# rf_lpf.net
KiCad netlist of a schematic drawn in Altium Designer
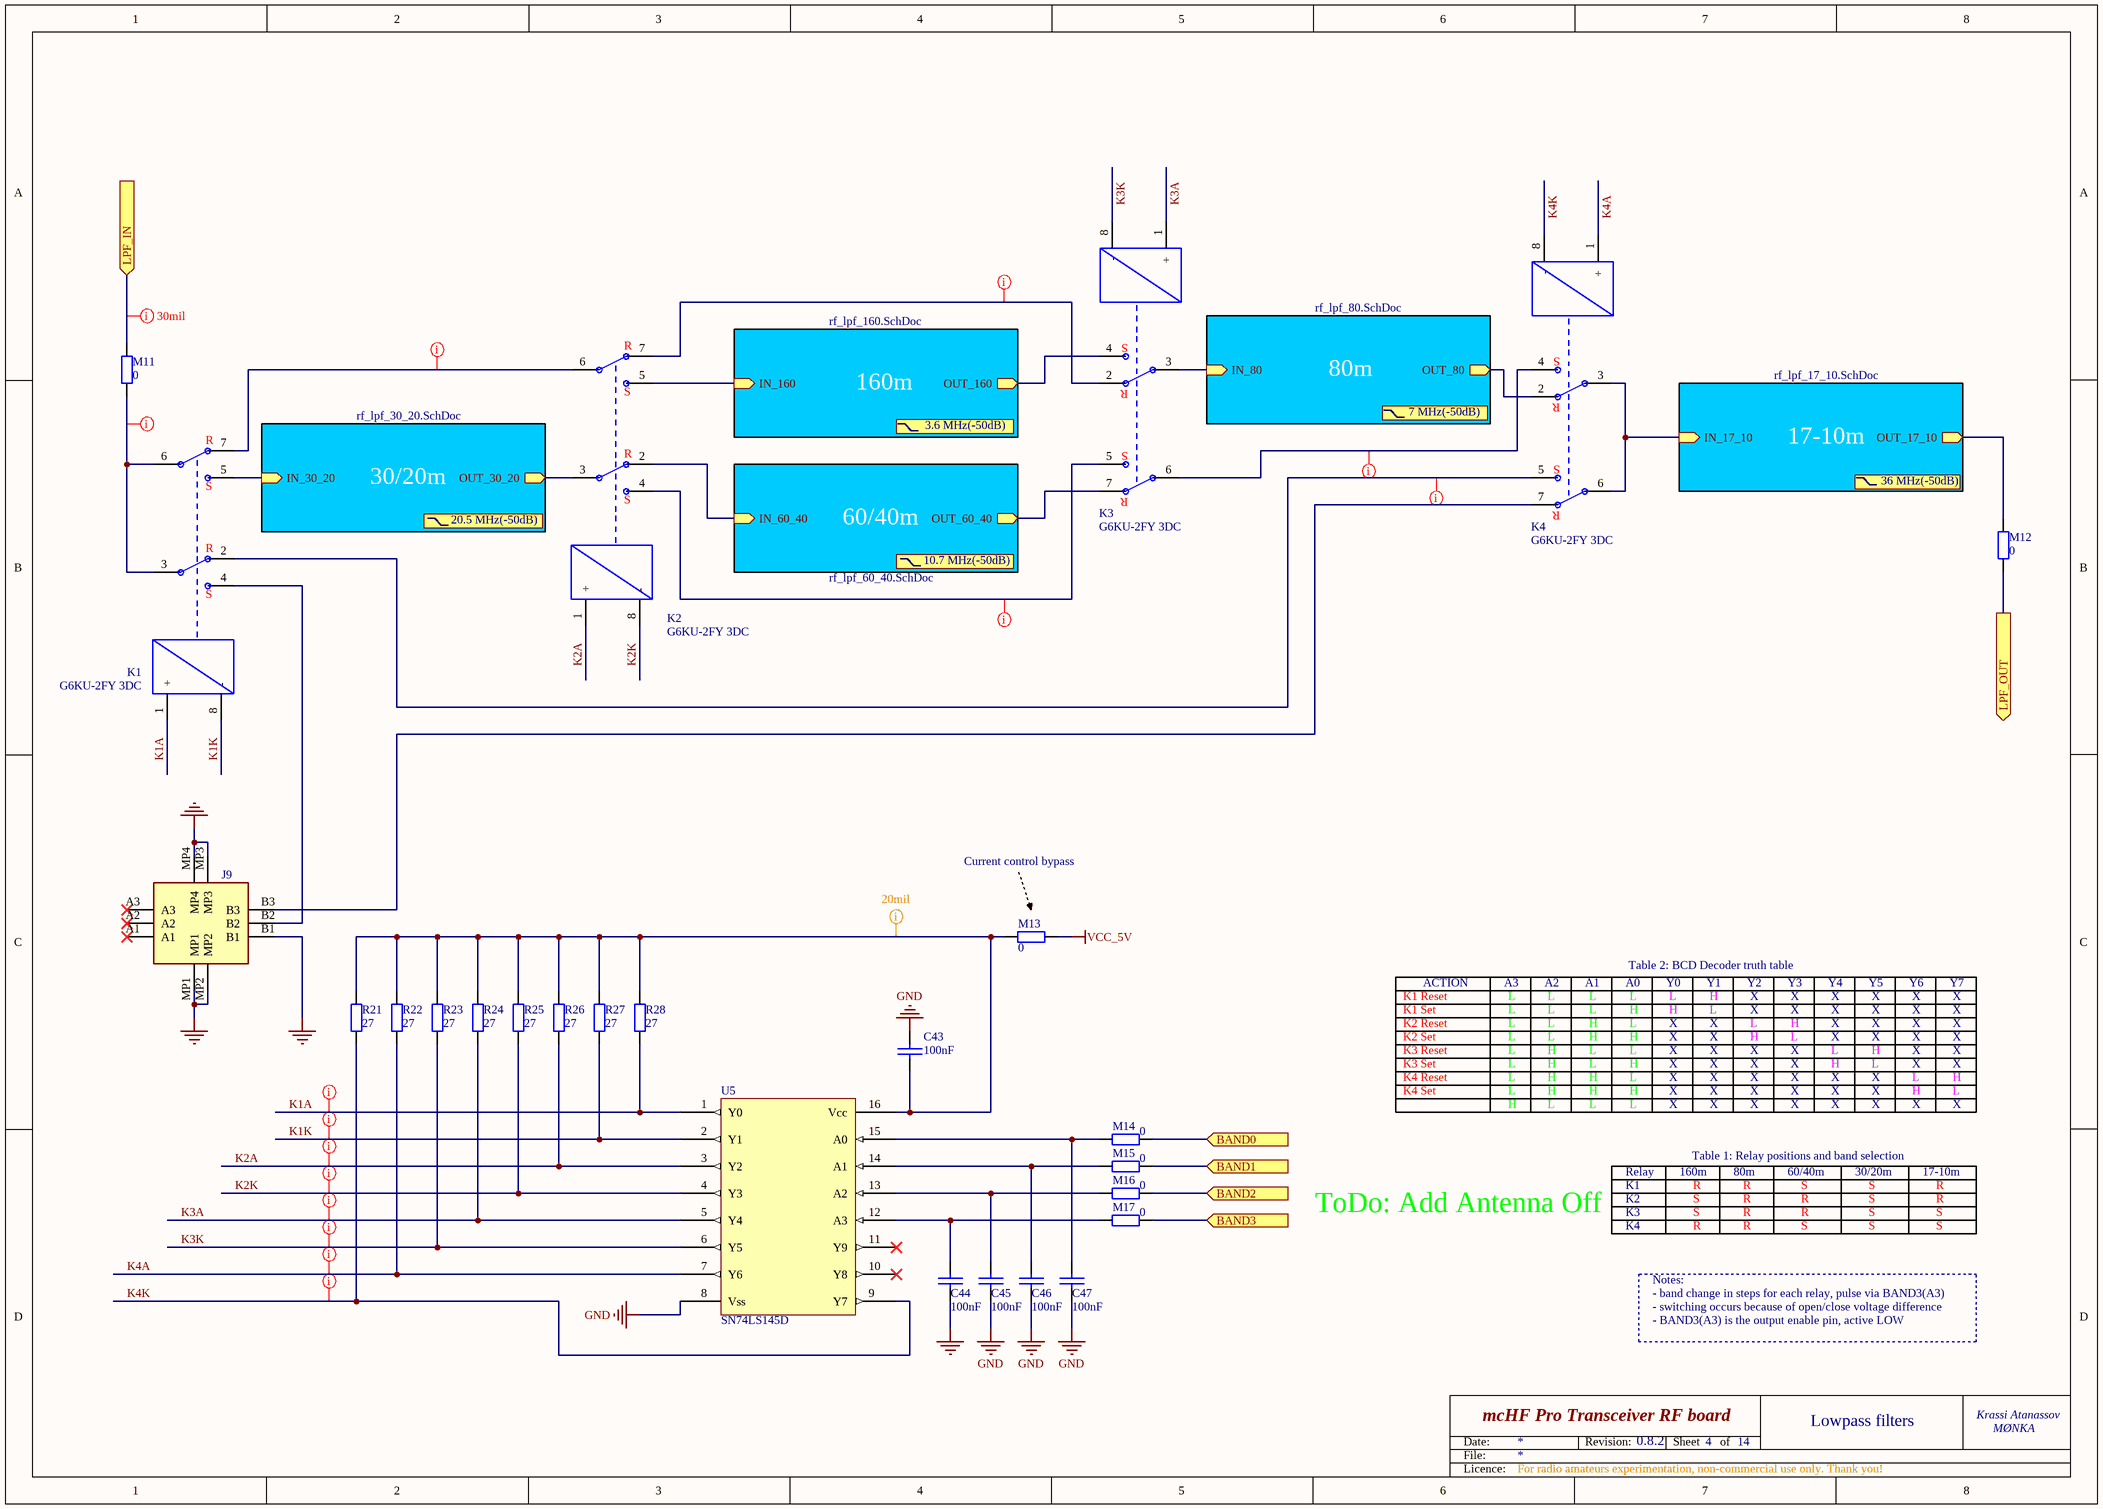
[diagram p0: rf_lpf.SchDoc]

(export (version "E")
  (design (tool "Eeschema 10.0.6"))
  (components
    (comp (ref "C43")
      (value "100nF")
      (footprint "0805")
      (description "Capacitor")
      (libsource (lib "mcHF_rf") (part "CAP"))
    )
    (comp (ref "C44")
      (value "100nF")
      (footprint "0805")
      (description "Capacitor")
      (libsource (lib "mcHF_rf") (part "CAP"))
    )
    (comp (ref "C45")
      (value "100nF")
      (footprint "0805")
      (description "Capacitor")
      (libsource (lib "mcHF_rf") (part "CAP"))
    )
    (comp (ref "C46")
      (value "100nF")
      (footprint "0805")
      (description "Capacitor")
      (libsource (lib "mcHF_rf") (part "CAP"))
    )
    (comp (ref "C47")
      (value "100nF")
      (footprint "0805")
      (description "Capacitor")
      (libsource (lib "mcHF_rf") (part "CAP"))
    )
    (comp (ref "J9")
      (value "1373826")
      (footprint "1373826")
      (fields (field (name "MOUSER PART NUMBER") "651-1373826"))
      (libsource (lib "1373826") (part "1373826"))
    )
    (comp (ref "K1")
      (value "G6KU-2FY 3DC")
      (footprint "Omron_2FY-Pro")
      (description "Single-winding Latching Relay")
      (libsource (lib "__rf") (part "G6KU-2FY 3DC"))
    )
    (comp (ref "K2")
      (value "G6KU-2FY 3DC")
      (footprint "Omron_2FY-Pro")
      (description "Single-winding Latching Relay")
      (libsource (lib "__rf") (part "G6KU-2FY 3DC"))
    )
    (comp (ref "K3")
      (value "G6KU-2FY 3DC")
      (footprint "Omron_2FY-Pro")
      (description "Single-winding Latching Relay")
      (libsource (lib "__rf") (part "G6KU-2FY 3DC"))
    )
    (comp (ref "K4")
      (value "G6KU-2FY 3DC")
      (footprint "Omron_2FY-Pro")
      (description "Single-winding Latching Relay")
      (libsource (lib "__rf") (part "G6KU-2FY 3DC"))
    )
    (comp (ref "M11")
      (value "0")
      (footprint "0805")
      (description "Resistor")
      (libsource (lib "") (part "RES_2"))
    )
    (comp (ref "M12")
      (value "0")
      (footprint "0805")
      (description "Resistor")
      (libsource (lib "") (part "RES_1"))
    )
    (comp (ref "M13")
      (value "0")
      (footprint "0805")
      (description "Resistor")
      (libsource (lib "") (part "RES_3"))
    )
    (comp (ref "M14")
      (value "0")
      (footprint "0805")
      (description "Resistor")
      (libsource (lib "mcHF_rf") (part "RES"))
    )
    (comp (ref "M15")
      (value "0")
      (footprint "0805")
      (description "Resistor")
      (libsource (lib "mcHF_rf") (part "RES"))
    )
    (comp (ref "M16")
      (value "0")
      (footprint "0805")
      (description "Resistor")
      (libsource (lib "mcHF_rf") (part "RES"))
    )
    (comp (ref "M17")
      (value "0")
      (footprint "0805")
      (description "Resistor")
      (libsource (lib "mcHF_rf") (part "RES"))
    )
    (comp (ref "R21")
      (value "27")
      (footprint "1206")
      (description "Resistor")
      (libsource (lib "") (part "RES_2"))
    )
    (comp (ref "R22")
      (value "27")
      (footprint "1206")
      (description "Resistor")
      (libsource (lib "") (part "RES_2"))
    )
    (comp (ref "R23")
      (value "27")
      (footprint "1206")
      (description "Resistor")
      (libsource (lib "") (part "RES_2"))
    )
    (comp (ref "R24")
      (value "27")
      (footprint "1206")
      (description "Resistor")
      (libsource (lib "") (part "RES_2"))
    )
    (comp (ref "R25")
      (value "27")
      (footprint "1206")
      (description "Resistor")
      (libsource (lib "") (part "RES_2"))
    )
    (comp (ref "R26")
      (value "27")
      (footprint "1206")
      (description "Resistor")
      (libsource (lib "") (part "RES_2"))
    )
    (comp (ref "R27")
      (value "27")
      (footprint "1206")
      (description "Resistor")
      (libsource (lib "") (part "RES_2"))
    )
    (comp (ref "R28")
      (value "27")
      (footprint "1206")
      (description "Resistor")
      (libsource (lib "") (part "RES_2"))
    )
    (comp (ref "U5")
      (value "SN74LS145D")
      (footprint "SO-16")
      (description "BCD DECODER/DRIVER")
      (libsource (lib "mcHF_rf") (part "SN74LS145D"))
    )
  )
  (nets
    (net (code "1") (name "/BAND0") (class "Default")
      (node (ref "M14") (pin "1") (pinfunction "1_1") (pintype "passive"))
    )
    (net (code "2") (name "/BAND1") (class "Default")
      (node (ref "M15") (pin "1") (pinfunction "1_1") (pintype "passive"))
    )
    (net (code "3") (name "/BAND2") (class "Default")
      (node (ref "M16") (pin "1") (pinfunction "1_1") (pintype "passive"))
    )
    (net (code "4") (name "/BAND3") (class "Default")
      (node (ref "M17") (pin "1") (pinfunction "1_1") (pintype "passive"))
    )
    (net (code "5") (name "/IN_17_10") (class "Default")
      (node (ref "K4") (pin "3") (pinfunction "3_3") (pintype "passive"))
      (node (ref "K4") (pin "6") (pinfunction "6_6") (pintype "passive"))
    )
    (net (code "6") (name "/IN_30_20") (class "Default")
      (node (ref "K1") (pin "5") (pinfunction "5_5") (pintype "passive"))
    )
    (net (code "7") (name "/IN_60_40") (class "Default")
      (node (ref "K2") (pin "2") (pinfunction "2_2") (pintype "passive"))
    )
    (net (code "8") (name "/IN_80") (class "Default")
      (node (ref "K3") (pin "3") (pinfunction "3_3") (pintype "passive"))
    )
    (net (code "9") (name "/IN_160") (class "Default")
      (node (ref "K2") (pin "5") (pinfunction "5_5") (pintype "passive"))
    )
    (net (code "10") (name "/K1A") (class "Default")
      (node (ref "K1") (pin "1") (pinfunction "+_1") (pintype "passive"))
      (node (ref "R28") (pin "1") (pinfunction "1_1") (pintype "passive"))
      (node (ref "U5") (pin "1") (pinfunction "Y0_1") (pintype "output"))
    )
    (net (code "11") (name "/K1K") (class "Default")
      (node (ref "K1") (pin "8") (pinfunction "-_8") (pintype "passive"))
      (node (ref "R27") (pin "1") (pinfunction "1_1") (pintype "passive"))
      (node (ref "U5") (pin "2") (pinfunction "Y1_2") (pintype "output"))
    )
    (net (code "12") (name "/K2A") (class "Default")
      (node (ref "K2") (pin "1") (pinfunction "+_1") (pintype "passive"))
      (node (ref "R26") (pin "1") (pinfunction "1_1") (pintype "passive"))
      (node (ref "U5") (pin "3") (pinfunction "Y2_3") (pintype "output"))
    )
    (net (code "13") (name "/K2K") (class "Default")
      (node (ref "K2") (pin "8") (pinfunction "-_8") (pintype "passive"))
      (node (ref "R25") (pin "1") (pinfunction "1_1") (pintype "passive"))
      (node (ref "U5") (pin "4") (pinfunction "Y3_4") (pintype "output"))
    )
    (net (code "14") (name "/K3A") (class "Default")
      (node (ref "K3") (pin "1") (pinfunction "+_1") (pintype "passive"))
      (node (ref "R24") (pin "1") (pinfunction "1_1") (pintype "passive"))
      (node (ref "U5") (pin "5") (pinfunction "Y4_5") (pintype "output"))
    )
    (net (code "15") (name "/K3K") (class "Default")
      (node (ref "K3") (pin "8") (pinfunction "-_8") (pintype "passive"))
      (node (ref "R23") (pin "1") (pinfunction "1_1") (pintype "passive"))
      (node (ref "U5") (pin "6") (pinfunction "Y5_6") (pintype "output"))
    )
    (net (code "16") (name "/K4A") (class "Default")
      (node (ref "K4") (pin "1") (pinfunction "+_1") (pintype "passive"))
      (node (ref "R22") (pin "1") (pinfunction "1_1") (pintype "passive"))
      (node (ref "U5") (pin "7") (pinfunction "Y6_7") (pintype "output"))
    )
    (net (code "17") (name "/K4K") (class "Default")
      (node (ref "K4") (pin "8") (pinfunction "-_8") (pintype "passive"))
      (node (ref "R21") (pin "1") (pinfunction "1_1") (pintype "passive"))
      (node (ref "U5") (pin "9") (pinfunction "Y7_9") (pintype "output"))
    )
    (net (code "18") (name "/LPF_IN") (class "Default")
      (node (ref "M11") (pin "2") (pinfunction "2_2") (pintype "passive"))
    )
    (net (code "19") (name "/LPF_OUT") (class "Default")
      (node (ref "M12") (pin "2") (pinfunction "2_2") (pintype "passive"))
    )
    (net (code "20") (name "/OUT_17_10") (class "Default")
      (node (ref "M12") (pin "1") (pinfunction "1_1") (pintype "passive"))
    )
    (net (code "21") (name "/OUT_30_20") (class "Default")
      (node (ref "K2") (pin "3") (pinfunction "3_3") (pintype "passive"))
    )
    (net (code "22") (name "/OUT_60_40") (class "Default")
      (node (ref "K3") (pin "7") (pinfunction "7_7") (pintype "passive"))
    )
    (net (code "23") (name "/OUT_80") (class "Default")
      (node (ref "K4") (pin "2") (pinfunction "2_2") (pintype "passive"))
    )
    (net (code "24") (name "/OUT_160") (class "Default")
      (node (ref "K3") (pin "4") (pinfunction "4_4") (pintype "passive"))
    )
    (net (code "25") (name "GND") (class "Default")
      (node (ref "C43") (pin "2") (pinfunction "2_2") (pintype "passive"))
      (node (ref "C44") (pin "1") (pinfunction "1_1") (pintype "passive"))
      (node (ref "C45") (pin "1") (pinfunction "1_1") (pintype "passive"))
      (node (ref "C46") (pin "1") (pinfunction "1_1") (pintype "passive"))
      (node (ref "C47") (pin "1") (pinfunction "1_1") (pintype "passive"))
      (node (ref "J9") (pin "B1") (pinfunction "B1_B1") (pintype "passive"))
      (node (ref "J9") (pin "MP1") (pinfunction "MP1_MP1") (pintype "passive"))
      (node (ref "J9") (pin "MP2") (pinfunction "MP2_MP2") (pintype "passive"))
      (node (ref "J9") (pin "MP3") (pinfunction "MP3_MP3") (pintype "passive"))
      (node (ref "J9") (pin "MP4") (pinfunction "MP4_MP4") (pintype "passive"))
      (node (ref "U5") (pin "8") (pinfunction "Vss_8") (pintype "power_in"))
    )
    (net (code "26") (name "Net-(J9-PadB2)") (class "Default")
      (node (ref "J9") (pin "B2") (pinfunction "B2_B2") (pintype "passive"))
      (node (ref "K1") (pin "4") (pinfunction "4_4") (pintype "passive"))
    )
    (net (code "27") (name "Net-(J9-PadB3)") (class "Default")
      (node (ref "J9") (pin "B3") (pinfunction "B3_B3") (pintype "passive"))
      (node (ref "K4") (pin "7") (pinfunction "7_7") (pintype "passive"))
    )
    (net (code "28") (name "Net-(K1-Pad2)") (class "Default")
      (node (ref "K1") (pin "2") (pinfunction "2_2") (pintype "passive"))
      (node (ref "K4") (pin "5") (pinfunction "5_5") (pintype "passive"))
    )
    (net (code "29") (name "Net-(K1-Pad3)") (class "Default")
      (node (ref "K1") (pin "3") (pinfunction "3_3") (pintype "passive"))
      (node (ref "K1") (pin "6") (pinfunction "6_6") (pintype "passive"))
      (node (ref "M11") (pin "1") (pinfunction "1_1") (pintype "passive"))
    )
    (net (code "30") (name "Net-(K1-Pad7)") (class "Default")
      (node (ref "K1") (pin "7") (pinfunction "7_7") (pintype "passive"))
      (node (ref "K2") (pin "6") (pinfunction "6_6") (pintype "passive"))
    )
    (net (code "31") (name "Net-(K2-Pad4)") (class "Default")
      (node (ref "K2") (pin "4") (pinfunction "4_4") (pintype "passive"))
      (node (ref "K3") (pin "5") (pinfunction "5_5") (pintype "passive"))
    )
    (net (code "32") (name "Net-(K2-Pad7)") (class "Default")
      (node (ref "K2") (pin "7") (pinfunction "7_7") (pintype "passive"))
      (node (ref "K3") (pin "2") (pinfunction "2_2") (pintype "passive"))
    )
    (net (code "33") (name "Net-(K3-Pad6)") (class "Default")
      (node (ref "K3") (pin "6") (pinfunction "6_6") (pintype "passive"))
      (node (ref "K4") (pin "4") (pinfunction "4_4") (pintype "passive"))
    )
    (net (code "34") (name "Net-(U5-A0)") (class "Default")
      (node (ref "C47") (pin "2") (pinfunction "2_2") (pintype "passive"))
      (node (ref "M14") (pin "2") (pinfunction "2_2") (pintype "passive"))
      (node (ref "U5") (pin "15") (pinfunction "A0_15") (pintype "input"))
    )
    (net (code "35") (name "Net-(U5-A1)") (class "Default")
      (node (ref "C46") (pin "2") (pinfunction "2_2") (pintype "passive"))
      (node (ref "M15") (pin "2") (pinfunction "2_2") (pintype "passive"))
      (node (ref "U5") (pin "14") (pinfunction "A1_14") (pintype "input"))
    )
    (net (code "36") (name "Net-(U5-A2)") (class "Default")
      (node (ref "C45") (pin "2") (pinfunction "2_2") (pintype "passive"))
      (node (ref "M16") (pin "2") (pinfunction "2_2") (pintype "passive"))
      (node (ref "U5") (pin "13") (pinfunction "A2_13") (pintype "input"))
    )
    (net (code "37") (name "Net-(U5-A3)") (class "Default")
      (node (ref "C44") (pin "2") (pinfunction "2_2") (pintype "passive"))
      (node (ref "M17") (pin "2") (pinfunction "2_2") (pintype "passive"))
      (node (ref "U5") (pin "12") (pinfunction "A3_12") (pintype "input"))
    )
    (net (code "38") (name "Net-(U5-Vcc)") (class "Default")
      (node (ref "C43") (pin "1") (pinfunction "1_1") (pintype "passive"))
      (node (ref "M13") (pin "1") (pinfunction "1_1") (pintype "passive"))
      (node (ref "R21") (pin "2") (pinfunction "2_2") (pintype "passive"))
      (node (ref "R22") (pin "2") (pinfunction "2_2") (pintype "passive"))
      (node (ref "R23") (pin "2") (pinfunction "2_2") (pintype "passive"))
      (node (ref "R24") (pin "2") (pinfunction "2_2") (pintype "passive"))
      (node (ref "R25") (pin "2") (pinfunction "2_2") (pintype "passive"))
      (node (ref "R26") (pin "2") (pinfunction "2_2") (pintype "passive"))
      (node (ref "R27") (pin "2") (pinfunction "2_2") (pintype "passive"))
      (node (ref "R28") (pin "2") (pinfunction "2_2") (pintype "passive"))
      (node (ref "U5") (pin "16") (pinfunction "Vcc_16") (pintype "power_in"))
    )
    (net (code "39") (name "VCC_5V") (class "Default")
      (node (ref "M13") (pin "2") (pinfunction "2_2") (pintype "passive"))
    )
    (net (code "40") (name "unconnected-(J9-PadA1)") (class "Default")
      (node (ref "J9") (pin "A1") (pinfunction "A1_A1") (pintype "passive+no_connect"))
    )
    (net (code "41") (name "unconnected-(J9-PadA2)") (class "Default")
      (node (ref "J9") (pin "A2") (pinfunction "A2_A2") (pintype "passive+no_connect"))
    )
    (net (code "42") (name "unconnected-(J9-PadA3)") (class "Default")
      (node (ref "J9") (pin "A3") (pinfunction "A3_A3") (pintype "passive+no_connect"))
    )
    (net (code "43") (name "unconnected-(U5-Y8-Pad10)") (class "Default")
      (node (ref "U5") (pin "10") (pinfunction "Y8_10") (pintype "output+no_connect"))
    )
    (net (code "44") (name "unconnected-(U5-Y9-Pad11)") (class "Default")
      (node (ref "U5") (pin "11") (pinfunction "Y9_11") (pintype "output+no_connect"))
    )
  )
)
